# MCU.net
KiCad netlist of a schematic drawn in Altium Designer
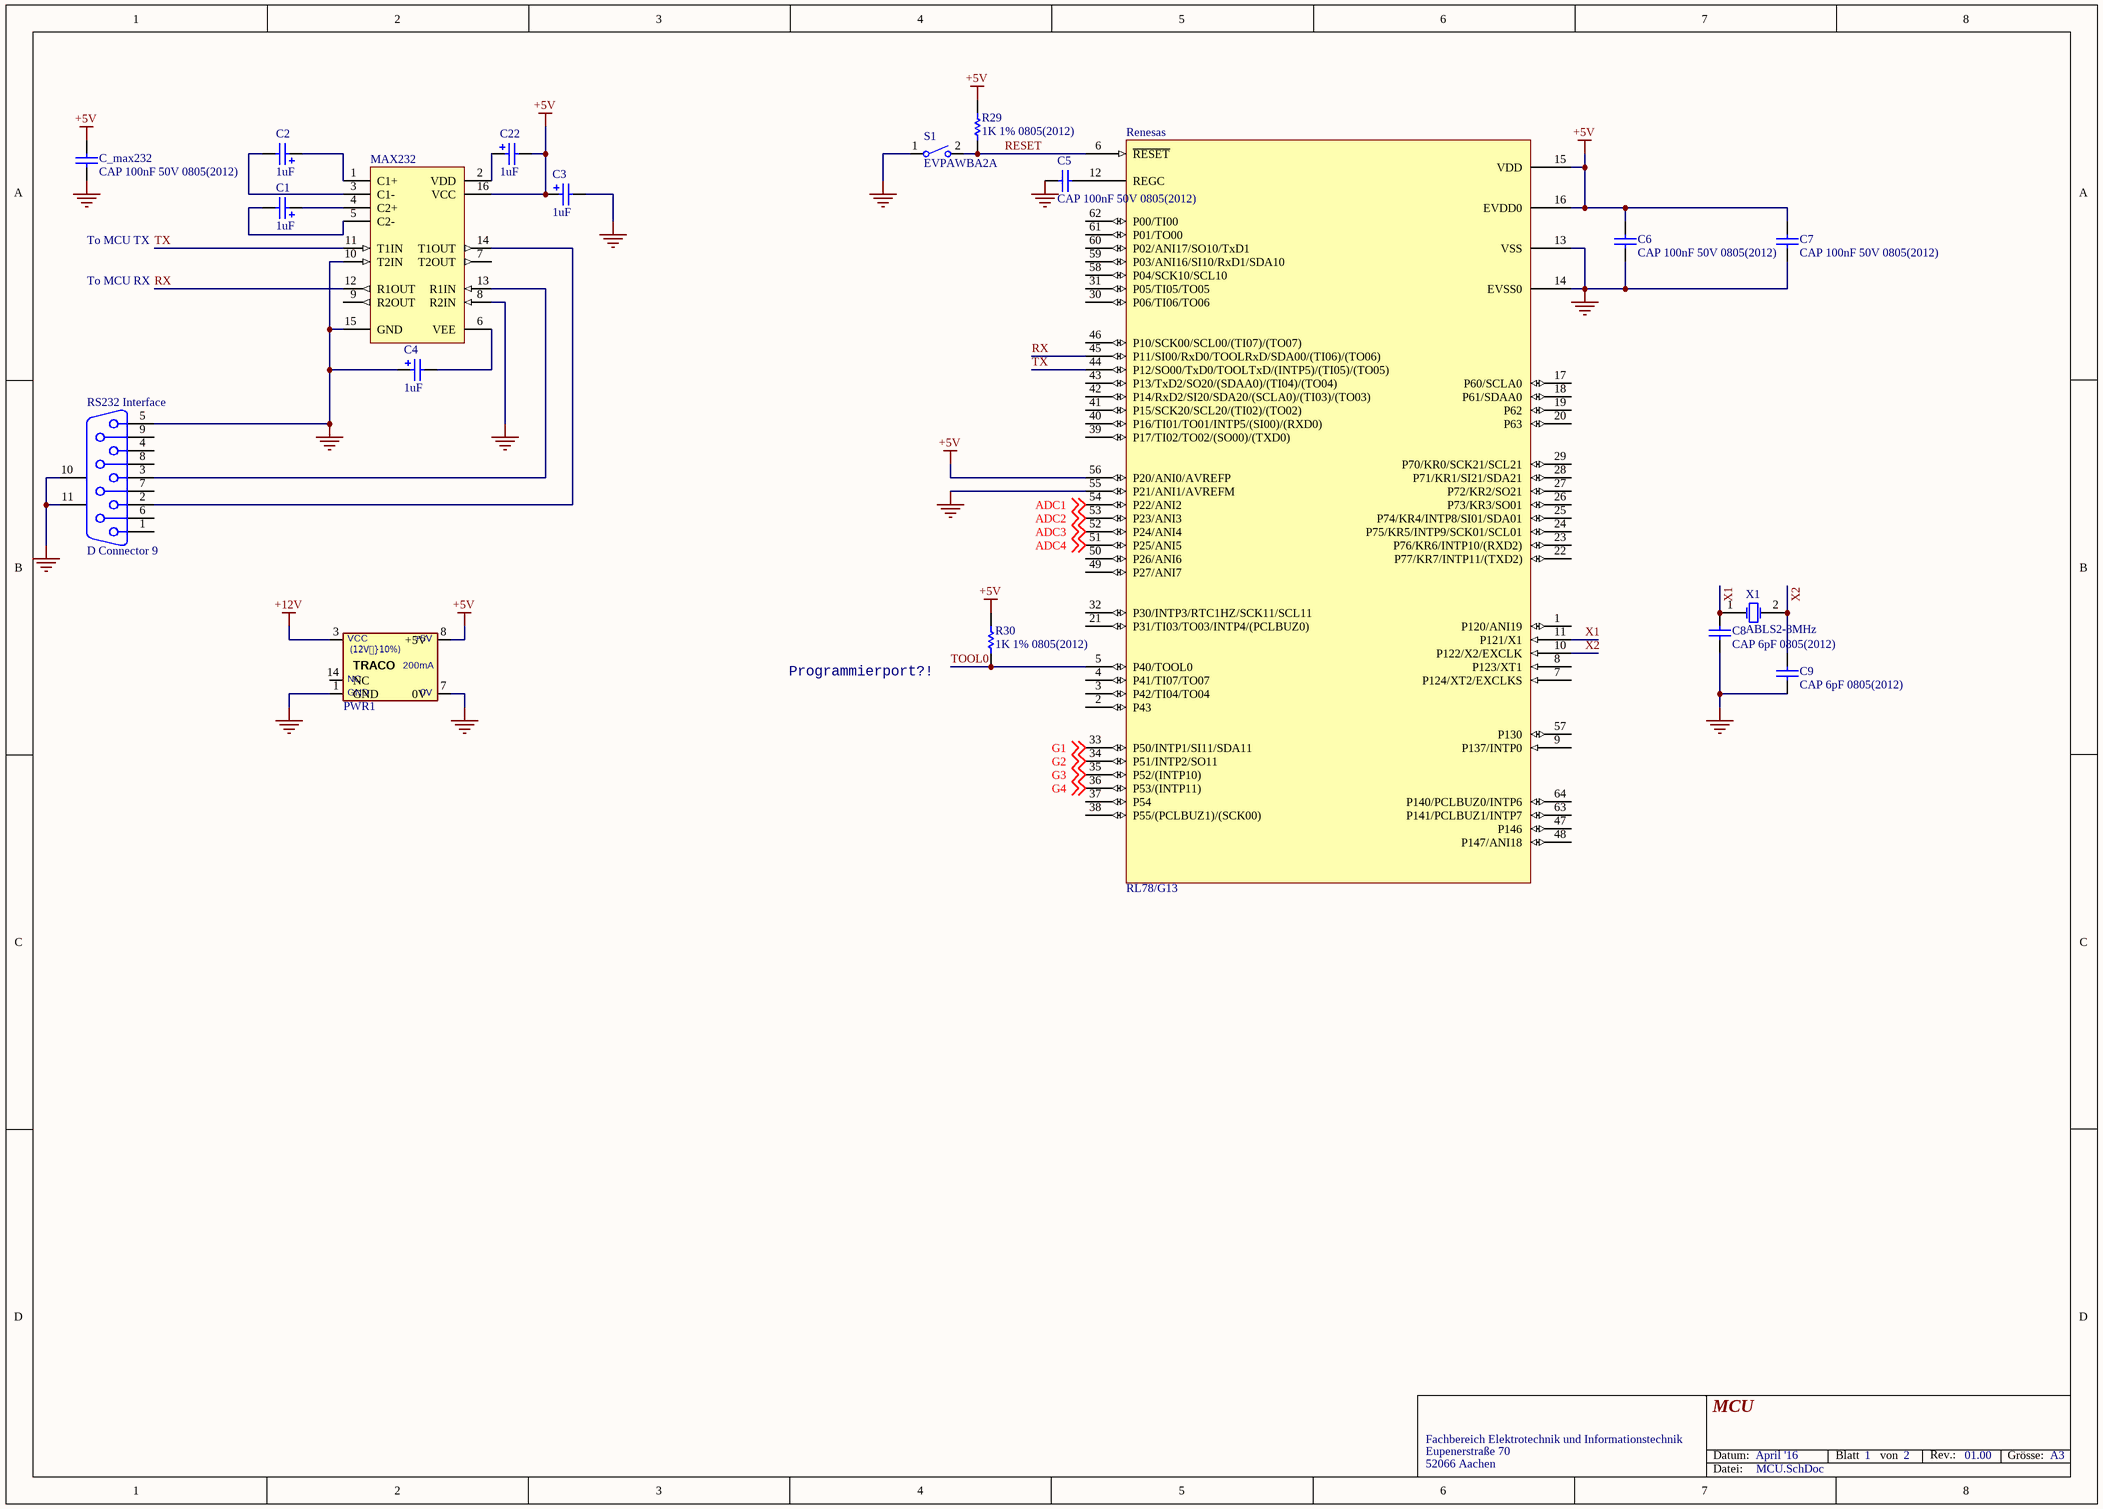
[diagram p0: MCU.SchDoc]

(export (version "E")
  (design (tool "Eeschema 10.0.6"))
  (components
    (comp (ref "C1")
      (value "1uF")
      (footprint "CC2012-0805")
      (description "Polarized Capacitor (Surface Mount)")
      (fields (field (name "Comment") "Cap Pol3") (field (name "PUBLISHER") "Altium Limited"))
      (libsource (lib "Miscellaneous Devices") (part "Cap Pol3"))
    )
    (comp (ref "C2")
      (value "1uF")
      (footprint "CC2012-0805")
      (description "Polarized Capacitor (Surface Mount)")
      (fields (field (name "Comment") "Cap Pol3") (field (name "PUBLISHER") "Altium Limited"))
      (libsource (lib "Miscellaneous Devices") (part "Cap Pol3"))
    )
    (comp (ref "C3")
      (value "1uF")
      (footprint "CC2012-0805")
      (description "Polarized Capacitor (Surface Mount)")
      (fields (field (name "Comment") "Cap Pol3") (field (name "PUBLISHER") "Altium Limited"))
      (libsource (lib "Miscellaneous Devices") (part "Cap Pol3"))
    )
    (comp (ref "C4")
      (value "1uF")
      (footprint "CC2012-0805")
      (description "Polarized Capacitor (Surface Mount)")
      (fields (field (name "Comment") "Cap Pol3") (field (name "PUBLISHER") "Altium Limited"))
      (libsource (lib "Miscellaneous Devices") (part "Cap Pol3"))
    )
    (comp (ref "C5")
      (value "CAP 100nF 50V 0805(2012)")
      (footprint "CAPC0805(2012)145_M")
      (description "CAP 100nF 50V ±10% 0805 (2012 Metric) Thickness 1.45mm SMD")
      (fields (field (name "TOLERANCE") "Â±10%"))
      (libsource (lib "Altium Content Vault") (part "CAP"))
    )
    (comp (ref "C6")
      (value "CAP 100nF 50V 0805(2012)")
      (footprint "CAPC0805(2012)145_M")
      (description "CAP 100nF 50V ±10% 0805 (2012 Metric) Thickness 1.45mm SMD")
      (fields (field (name "TOLERANCE") "Â±10%"))
      (libsource (lib "Altium Content Vault") (part "CAP"))
    )
    (comp (ref "C7")
      (value "CAP 100nF 50V 0805(2012)")
      (footprint "CAPC0805(2012)145_M")
      (description "CAP 100nF 50V ±10% 0805 (2012 Metric) Thickness 1.45mm SMD")
      (fields (field (name "TOLERANCE") "Â±10%"))
      (libsource (lib "Altium Content Vault") (part "CAP"))
    )
    (comp (ref "C8")
      (value "CAP 6pF 0805(2012)")
      (footprint "CAPC0805(2012)145_M")
      (description "CAP 100nF 50V ±10% 0805 (2012 Metric) Thickness 1.45mm SMD")
      (fields (field (name "TOLERANCE") "Â±10%"))
      (libsource (lib "Altium Content Vault") (part "CAP"))
    )
    (comp (ref "C9")
      (value "CAP 6pF 0805(2012)")
      (footprint "CAPC0805(2012)145_M")
      (description "CAP 100nF 50V ±10% 0805 (2012 Metric) Thickness 1.45mm SMD")
      (fields (field (name "TOLERANCE") "Â±10%"))
      (libsource (lib "Altium Content Vault") (part "CAP"))
    )
    (comp (ref "C22")
      (value "1uF")
      (footprint "CC2012-0805")
      (description "Polarized Capacitor (Surface Mount)")
      (fields (field (name "Comment") "Cap Pol3") (field (name "PUBLISHER") "Altium Limited"))
      (libsource (lib "Miscellaneous Devices") (part "Cap Pol3"))
    )
    (comp (ref "C_max232")
      (value "CAP 100nF 50V 0805(2012)")
      (footprint "CAPC0805(2012)145_M")
      (description "CAP 100nF 50V ±10% 0805 (2012 Metric) Thickness 1.45mm SMD")
      (fields (field (name "TOLERANCE") "Â±10%"))
      (libsource (lib "Altium Content Vault") (part "CAP"))
    )
    (comp (ref "MAX232")
      (value "MAX232CSE")
      (footprint "NSO16")
      (description "+5V Powered, Multi-Channel RS-232 Driver/Receiver")
      (fields (field (name "PUBLISHER") "Altium Limited"))
      (libsource (lib "Maxim Communication Transceiver") (part "MAX232CSE"))
    )
    (comp (ref "PWR1")
      (value "TES1-1211")
      (footprint "TES14")
      (description "Input=12V}10% Output=5V 200mA 1W 1500VDC Isolation SMD14 RoHS")
      (libsource (lib "TRACO_TES1_e") (part "TES1-1211"))
    )
    (comp (ref "R29")
      (value "1K 1% 0805(2012)")
      (footprint "RESC0805(2012)_M")
      (description "10K 0.125W 1% 0805 (2012 Metric)  SMD")
      (fields (field (name "TOLERANCE") "1 %") (field (name "POWER") "0.125 W"))
      (libsource (lib "Altium Content Vault") (part "CMP-1013-00623-1"))
    )
    (comp (ref "R30")
      (value "1K 1% 0805(2012)")
      (footprint "RESC0805(2012)_M")
      (description "10K 0.125W 1% 0805 (2012 Metric)  SMD")
      (fields (field (name "TOLERANCE") "1 %") (field (name "POWER") "0.125 W"))
      (libsource (lib "Altium Content Vault") (part "CMP-1013-00623-1"))
    )
    (comp (ref "Renesas")
      (value "RL78/G13")
      (footprint "R5F100LEAFA - duplicate")
      (libsource (lib "RenesasRL78") (part "RL78/G13"))
    )
    (comp (ref "RS232 Interface")
      (value "D Connector 9")
      (footprint "DSUB1.385-2H9")
      (description "Receptacle Assembly, 9 Position, Right Angle")
      (fields (field (name "PUBLISHER") "Altium Limited"))
      (libsource (lib "Miscellaneous Connectors") (part "D Connector 9"))
    )
    (comp (ref "S1")
      (value "EVPAWBA2A")
      (footprint "PNSC-EVPAW_V")
      (fields (field (name "MANUFACTURER") "Panasonic"))
      (libsource (lib "Altium Content Vault") (part "PNSC-SPST-2"))
    )
    (comp (ref "X1")
      (value "ABLS2-8MHz")
      (footprint "ABRA-ABLS2-2_V")
      (fields (field (name "MANUFACTURER") "Abracon") (field (name "PARTNUMBER") "ABLS2-4.096MHZ-D4Y-T"))
      (libsource (lib "Altium Content Vault") (part "ABRA-XTAL_1-2-2"))
    )
  )
  (nets
    (net (code "1") (name "+5V") (class "Default")
      (node (ref "C22") (pin "2") (pinfunction "2_2") (pintype "passive"))
      (node (ref "C3") (pin "1") (pinfunction "1_1") (pintype "passive"))
      (node (ref "C6") (pin "2") (pinfunction "2_2") (pintype "passive"))
      (node (ref "C7") (pin "2") (pinfunction "2_2") (pintype "passive"))
      (node (ref "C_max232") (pin "2") (pinfunction "2_2") (pintype "passive"))
      (node (ref "MAX232") (pin "16") (pinfunction "VCC_16") (pintype "power_in"))
      (node (ref "PWR1") (pin "8") (pinfunction "+5V_8") (pintype "power_in"))
      (node (ref "R29") (pin "1") (pinfunction "1_1") (pintype "passive"))
      (node (ref "R30") (pin "1") (pinfunction "1_1") (pintype "passive"))
      (node (ref "Renesas") (pin "15") (pinfunction "VDD_15") (pintype "power_in"))
      (node (ref "Renesas") (pin "16") (pinfunction "EVDD0_16") (pintype "power_in"))
      (node (ref "Renesas") (pin "56") (pinfunction "P20/ANI0/AVREFP_56") (pintype "bidirectional"))
    )
    (net (code "2") (name "+12V") (class "Default")
      (node (ref "PWR1") (pin "3") (pinfunction "VCC_3") (pintype "power_in"))
    )
    (net (code "3") (name "/RESET") (class "Default")
      (node (ref "R29") (pin "2") (pinfunction "2_2") (pintype "passive"))
      (node (ref "Renesas") (pin "6") (pinfunction "~{RESET}_6") (pintype "input"))
      (node (ref "S1") (pin "2") (pinfunction "B1_2") (pintype "passive"))
    )
    (net (code "4") (name "/RX") (class "Default")
      (node (ref "MAX232") (pin "12") (pinfunction "R1OUT_12") (pintype "output"))
      (node (ref "Renesas") (pin "45") (pinfunction "P11/SI00/RxD0/TOOLRxD/SDA00/(TI06)/(TO06)_45") (pintype "bidirectional"))
    )
    (net (code "5") (name "/TOOL0") (class "Default")
      (node (ref "R30") (pin "2") (pinfunction "2_2") (pintype "passive"))
      (node (ref "Renesas") (pin "5") (pinfunction "P40/TOOL0_5") (pintype "bidirectional"))
    )
    (net (code "6") (name "/TX") (class "Default")
      (node (ref "MAX232") (pin "11") (pinfunction "T1IN_11") (pintype "input"))
      (node (ref "Renesas") (pin "44") (pinfunction "P12/SO00/TxD0/TOOLTxD/(INTP5)/(TI05)/(TO05)_44") (pintype "bidirectional"))
    )
    (net (code "7") (name "/X1") (class "Default")
      (node (ref "C8") (pin "2") (pinfunction "2_2") (pintype "passive"))
      (node (ref "Renesas") (pin "11") (pinfunction "P121/X1_11") (pintype "input"))
      (node (ref "X1") (pin "1") (pinfunction "X1_1") (pintype "passive"))
    )
    (net (code "8") (name "/X2") (class "Default")
      (node (ref "C9") (pin "2") (pinfunction "2_2") (pintype "passive"))
      (node (ref "Renesas") (pin "10") (pinfunction "P122/X2/EXCLK_10") (pintype "input"))
      (node (ref "X1") (pin "2") (pinfunction "X2_2") (pintype "passive"))
    )
    (net (code "9") (name "ADC1") (class "Default")
      (node (ref "Renesas") (pin "54") (pinfunction "P22/ANI2_54") (pintype "bidirectional"))
    )
    (net (code "10") (name "ADC2") (class "Default")
      (node (ref "Renesas") (pin "53") (pinfunction "P23/ANI3_53") (pintype "bidirectional"))
    )
    (net (code "11") (name "ADC3") (class "Default")
      (node (ref "Renesas") (pin "52") (pinfunction "P24/ANI4_52") (pintype "bidirectional"))
    )
    (net (code "12") (name "ADC4") (class "Default")
      (node (ref "Renesas") (pin "51") (pinfunction "P25/ANI5_51") (pintype "bidirectional"))
    )
    (net (code "13") (name "G1") (class "Default")
      (node (ref "Renesas") (pin "33") (pinfunction "P50/INTP1/SI11/SDA11_33") (pintype "bidirectional"))
    )
    (net (code "14") (name "G2") (class "Default")
      (node (ref "Renesas") (pin "34") (pinfunction "P51/INTP2/SO11_34") (pintype "bidirectional"))
    )
    (net (code "15") (name "G3") (class "Default")
      (node (ref "Renesas") (pin "35") (pinfunction "P52/(INTP10)_35") (pintype "bidirectional"))
    )
    (net (code "16") (name "G4") (class "Default")
      (node (ref "Renesas") (pin "36") (pinfunction "P53/(INTP11)_36") (pintype "bidirectional"))
    )
    (net (code "17") (name "GND") (class "Default")
      (node (ref "C3") (pin "2") (pinfunction "2_2") (pintype "passive"))
      (node (ref "C4") (pin "1") (pinfunction "1_1") (pintype "passive"))
      (node (ref "C5") (pin "2") (pinfunction "2_2") (pintype "passive"))
      (node (ref "C6") (pin "1") (pinfunction "1_1") (pintype "passive"))
      (node (ref "C7") (pin "1") (pinfunction "1_1") (pintype "passive"))
      (node (ref "C8") (pin "1") (pinfunction "1_1") (pintype "passive"))
      (node (ref "C9") (pin "1") (pinfunction "1_1") (pintype "passive"))
      (node (ref "C_max232") (pin "1") (pinfunction "1_1") (pintype "passive"))
      (node (ref "MAX232") (pin "10") (pinfunction "T2IN_10") (pintype "input"))
      (node (ref "MAX232") (pin "15") (pinfunction "GND_15") (pintype "power_in"))
      (node (ref "MAX232") (pin "8") (pinfunction "R2IN_8") (pintype "input"))
      (node (ref "PWR1") (pin "1") (pinfunction "GND_1") (pintype "power_in"))
      (node (ref "PWR1") (pin "7") (pinfunction "0V_7") (pintype "power_in"))
      (node (ref "RS232 Interface") (pin "10") (pinfunction "MH1_10") (pintype "passive"))
      (node (ref "RS232 Interface") (pin "11") (pinfunction "MH2_11") (pintype "passive"))
      (node (ref "RS232 Interface") (pin "5") (pinfunction "5_5") (pintype "passive"))
      (node (ref "Renesas") (pin "13") (pinfunction "VSS_13") (pintype "power_in"))
      (node (ref "Renesas") (pin "14") (pinfunction "EVSS0_14") (pintype "power_in"))
      (node (ref "Renesas") (pin "55") (pinfunction "P21/ANI1/AVREFM_55") (pintype "bidirectional"))
      (node (ref "S1") (pin "1") (pinfunction "A1_1") (pintype "passive"))
    )
    (net (code "18") (name "Net-(MAX232-C1+)") (class "Default")
      (node (ref "C2") (pin "1") (pinfunction "1_1") (pintype "passive"))
      (node (ref "MAX232") (pin "1") (pinfunction "C1+_1") (pintype "passive"))
    )
    (net (code "19") (name "Net-(MAX232-C1-)") (class "Default")
      (node (ref "C2") (pin "2") (pinfunction "2_2") (pintype "passive"))
      (node (ref "MAX232") (pin "3") (pinfunction "C1-_3") (pintype "passive"))
    )
    (net (code "20") (name "Net-(MAX232-C2+)") (class "Default")
      (node (ref "C1") (pin "1") (pinfunction "1_1") (pintype "passive"))
      (node (ref "MAX232") (pin "4") (pinfunction "C2+_4") (pintype "passive"))
    )
    (net (code "21") (name "Net-(MAX232-C2-)") (class "Default")
      (node (ref "C1") (pin "2") (pinfunction "2_2") (pintype "passive"))
      (node (ref "MAX232") (pin "5") (pinfunction "C2-_5") (pintype "passive"))
    )
    (net (code "22") (name "Net-(MAX232-R1IN)") (class "Default")
      (node (ref "MAX232") (pin "13") (pinfunction "R1IN_13") (pintype "input"))
      (node (ref "RS232 Interface") (pin "3") (pinfunction "3_3") (pintype "passive"))
    )
    (net (code "23") (name "Net-(MAX232-T1OUT)") (class "Default")
      (node (ref "MAX232") (pin "14") (pinfunction "T1OUT_14") (pintype "output"))
      (node (ref "RS232 Interface") (pin "2") (pinfunction "2_2") (pintype "passive"))
    )
    (net (code "24") (name "Net-(MAX232-VDD)") (class "Default")
      (node (ref "C22") (pin "1") (pinfunction "1_1") (pintype "passive"))
      (node (ref "MAX232") (pin "2") (pinfunction "VDD_2") (pintype "power_in"))
    )
    (net (code "25") (name "Net-(MAX232-VEE)") (class "Default")
      (node (ref "C4") (pin "2") (pinfunction "2_2") (pintype "passive"))
      (node (ref "MAX232") (pin "6") (pinfunction "VEE_6") (pintype "power_in"))
    )
    (net (code "26") (name "Net-(Renesas-REGC)") (class "Default")
      (node (ref "C5") (pin "1") (pinfunction "1_1") (pintype "passive"))
      (node (ref "Renesas") (pin "12") (pinfunction "REGC_12") (pintype "passive"))
    )
    (net (code "27") (name "unconnected-(MAX232-R2OUT-Pad9)") (class "Default")
      (node (ref "MAX232") (pin "9") (pinfunction "R2OUT_9") (pintype "output"))
    )
    (net (code "28") (name "unconnected-(MAX232-T2OUT-Pad7)") (class "Default")
      (node (ref "MAX232") (pin "7") (pinfunction "T2OUT_7") (pintype "output"))
    )
    (net (code "29") (name "unconnected-(PWR1-NC-Pad14)") (class "Default")
      (node (ref "PWR1") (pin "14") (pinfunction "NC_14") (pintype "passive"))
    )
    (net (code "30") (name "unconnected-(RS232 Interface-Pad1)") (class "Default")
      (node (ref "RS232 Interface") (pin "1") (pinfunction "1_1") (pintype "passive"))
    )
    (net (code "31") (name "unconnected-(RS232 Interface-Pad4)") (class "Default")
      (node (ref "RS232 Interface") (pin "4") (pinfunction "4_4") (pintype "passive"))
    )
    (net (code "32") (name "unconnected-(RS232 Interface-Pad6)") (class "Default")
      (node (ref "RS232 Interface") (pin "6") (pinfunction "6_6") (pintype "passive"))
    )
    (net (code "33") (name "unconnected-(RS232 Interface-Pad7)") (class "Default")
      (node (ref "RS232 Interface") (pin "7") (pinfunction "7_7") (pintype "passive"))
    )
    (net (code "34") (name "unconnected-(RS232 Interface-Pad8)") (class "Default")
      (node (ref "RS232 Interface") (pin "8") (pinfunction "8_8") (pintype "passive"))
    )
    (net (code "35") (name "unconnected-(RS232 Interface-Pad9)") (class "Default")
      (node (ref "RS232 Interface") (pin "9") (pinfunction "9_9") (pintype "passive"))
    )
    (net (code "36") (name "unconnected-(Renesas-P00{slash}TI00-Pad62)") (class "Default")
      (node (ref "Renesas") (pin "62") (pinfunction "P00/TI00_62") (pintype "bidirectional"))
    )
    (net (code "37") (name "unconnected-(Renesas-P01{slash}TO00-Pad61)") (class "Default")
      (node (ref "Renesas") (pin "61") (pinfunction "P01/TO00_61") (pintype "bidirectional"))
    )
    (net (code "38") (name "unconnected-(Renesas-P02{slash}ANI17{slash}SO10{slash}TxD1-Pad60)") (class "Default")
      (node (ref "Renesas") (pin "60") (pinfunction "P02/ANI17/SO10/TxD1_60") (pintype "bidirectional"))
    )
    (net (code "39") (name "unconnected-(Renesas-P03{slash}ANI16{slash}SI10{slash}RxD1{slash}SDA10-Pad59)") (class "Default")
      (node (ref "Renesas") (pin "59") (pinfunction "P03/ANI16/SI10/RxD1/SDA10_59") (pintype "bidirectional"))
    )
    (net (code "40") (name "unconnected-(Renesas-P04{slash}SCK10{slash}SCL10-Pad58)") (class "Default")
      (node (ref "Renesas") (pin "58") (pinfunction "P04/SCK10/SCL10_58") (pintype "bidirectional"))
    )
    (net (code "41") (name "unconnected-(Renesas-P05{slash}TI05{slash}TO05-Pad31)") (class "Default")
      (node (ref "Renesas") (pin "31") (pinfunction "P05/TI05/TO05_31") (pintype "bidirectional"))
    )
    (net (code "42") (name "unconnected-(Renesas-P06{slash}TI06{slash}TO06-Pad30)") (class "Default")
      (node (ref "Renesas") (pin "30") (pinfunction "P06/TI06/TO06_30") (pintype "bidirectional"))
    )
    (net (code "43") (name "unconnected-(Renesas-P10{slash}SCK00{slash}SCL00{slash}(TI07){slash}(TO07)-Pad46)") (class "Default")
      (node (ref "Renesas") (pin "46") (pinfunction "P10/SCK00/SCL00/(TI07)/(TO07)_46") (pintype "bidirectional"))
    )
    (net (code "44") (name "unconnected-(Renesas-P13{slash}TxD2{slash}SO20{slash}(SDAA0){slash}(TI04){slash}(TO04)-Pad43)") (class "Default")
      (node (ref "Renesas") (pin "43") (pinfunction "P13/TxD2/SO20/(SDAA0)/(TI04)/(TO04)_43") (pintype "bidirectional"))
    )
    (net (code "45") (name "unconnected-(Renesas-P14{slash}RxD2{slash}SI20{slash}SDA20{slash}(SCLA0){slash}(TI03){slash}(TO03)-Pad42)") (class "Default")
      (node (ref "Renesas") (pin "42") (pinfunction "P14/RxD2/SI20/SDA20/(SCLA0)/(TI03)/(TO03)_42") (pintype "bidirectional"))
    )
    (net (code "46") (name "unconnected-(Renesas-P15{slash}SCK20{slash}SCL20{slash}(TI02){slash}(TO02)-Pad41)") (class "Default")
      (node (ref "Renesas") (pin "41") (pinfunction "P15/SCK20/SCL20/(TI02)/(TO02)_41") (pintype "bidirectional"))
    )
    (net (code "47") (name "unconnected-(Renesas-P16{slash}TI01{slash}TO01{slash}INTP5{slash}(SI00){slash}(RXD0)-Pad40)") (class "Default")
      (node (ref "Renesas") (pin "40") (pinfunction "P16/TI01/TO01/INTP5/(SI00)/(RXD0)_40") (pintype "bidirectional"))
    )
    (net (code "48") (name "unconnected-(Renesas-P17{slash}TI02{slash}TO02{slash}(SO00){slash}(TXD0)-Pad39)") (class "Default")
      (node (ref "Renesas") (pin "39") (pinfunction "P17/TI02/TO02/(SO00)/(TXD0)_39") (pintype "bidirectional"))
    )
    (net (code "49") (name "unconnected-(Renesas-P26{slash}ANI6-Pad50)") (class "Default")
      (node (ref "Renesas") (pin "50") (pinfunction "P26/ANI6_50") (pintype "bidirectional"))
    )
    (net (code "50") (name "unconnected-(Renesas-P27{slash}ANI7-Pad49)") (class "Default")
      (node (ref "Renesas") (pin "49") (pinfunction "P27/ANI7_49") (pintype "bidirectional"))
    )
    (net (code "51") (name "unconnected-(Renesas-P30{slash}INTP3{slash}RTC1HZ{slash}SCK11{slash}SCL11-Pad32)") (class "Default")
      (node (ref "Renesas") (pin "32") (pinfunction "P30/INTP3/RTC1HZ/SCK11/SCL11_32") (pintype "bidirectional"))
    )
    (net (code "52") (name "unconnected-(Renesas-P31{slash}TI03{slash}TO03{slash}INTP4{slash}(PCLBUZ0)-Pad21)") (class "Default")
      (node (ref "Renesas") (pin "21") (pinfunction "P31/TI03/TO03/INTP4/(PCLBUZ0)_21") (pintype "bidirectional"))
    )
    (net (code "53") (name "unconnected-(Renesas-P41{slash}TI07{slash}TO07-Pad4)") (class "Default")
      (node (ref "Renesas") (pin "4") (pinfunction "P41/TI07/TO07_4") (pintype "bidirectional"))
    )
    (net (code "54") (name "unconnected-(Renesas-P42{slash}TI04{slash}TO04-Pad3)") (class "Default")
      (node (ref "Renesas") (pin "3") (pinfunction "P42/TI04/TO04_3") (pintype "bidirectional"))
    )
    (net (code "55") (name "unconnected-(Renesas-P43-Pad2)") (class "Default")
      (node (ref "Renesas") (pin "2") (pinfunction "P43_2") (pintype "bidirectional"))
    )
    (net (code "56") (name "unconnected-(Renesas-P54-Pad37)") (class "Default")
      (node (ref "Renesas") (pin "37") (pinfunction "P54_37") (pintype "bidirectional"))
    )
    (net (code "57") (name "unconnected-(Renesas-P55{slash}(PCLBUZ1){slash}(SCK00)-Pad38)") (class "Default")
      (node (ref "Renesas") (pin "38") (pinfunction "P55/(PCLBUZ1)/(SCK00)_38") (pintype "bidirectional"))
    )
    (net (code "58") (name "unconnected-(Renesas-P60{slash}SCLA0-Pad17)") (class "Default")
      (node (ref "Renesas") (pin "17") (pinfunction "P60/SCLA0_17") (pintype "bidirectional"))
    )
    (net (code "59") (name "unconnected-(Renesas-P61{slash}SDAA0-Pad18)") (class "Default")
      (node (ref "Renesas") (pin "18") (pinfunction "P61/SDAA0_18") (pintype "bidirectional"))
    )
    (net (code "60") (name "unconnected-(Renesas-P62-Pad19)") (class "Default")
      (node (ref "Renesas") (pin "19") (pinfunction "P62_19") (pintype "bidirectional"))
    )
    (net (code "61") (name "unconnected-(Renesas-P63-Pad20)") (class "Default")
      (node (ref "Renesas") (pin "20") (pinfunction "P63_20") (pintype "bidirectional"))
    )
    (net (code "62") (name "unconnected-(Renesas-P70{slash}KR0{slash}SCK21{slash}SCL21-Pad29)") (class "Default")
      (node (ref "Renesas") (pin "29") (pinfunction "P70/KR0/SCK21/SCL21_29") (pintype "bidirectional"))
    )
    (net (code "63") (name "unconnected-(Renesas-P71{slash}KR1{slash}SI21{slash}SDA21-Pad28)") (class "Default")
      (node (ref "Renesas") (pin "28") (pinfunction "P71/KR1/SI21/SDA21_28") (pintype "bidirectional"))
    )
    (net (code "64") (name "unconnected-(Renesas-P72{slash}KR2{slash}SO21-Pad27)") (class "Default")
      (node (ref "Renesas") (pin "27") (pinfunction "P72/KR2/SO21_27") (pintype "bidirectional"))
    )
    (net (code "65") (name "unconnected-(Renesas-P73{slash}KR3{slash}SO01-Pad26)") (class "Default")
      (node (ref "Renesas") (pin "26") (pinfunction "P73/KR3/SO01_26") (pintype "bidirectional"))
    )
    (net (code "66") (name "unconnected-(Renesas-P74{slash}KR4{slash}INTP8{slash}SI01{slash}SDA01-Pad25)") (class "Default")
      (node (ref "Renesas") (pin "25") (pinfunction "P74/KR4/INTP8/SI01/SDA01_25") (pintype "bidirectional"))
    )
    (net (code "67") (name "unconnected-(Renesas-P75{slash}KR5{slash}INTP9{slash}SCK01{slash}SCL01-Pad24)") (class "Default")
      (node (ref "Renesas") (pin "24") (pinfunction "P75/KR5/INTP9/SCK01/SCL01_24") (pintype "bidirectional"))
    )
    (net (code "68") (name "unconnected-(Renesas-P76{slash}KR6{slash}INTP10{slash}(RXD2)-Pad23)") (class "Default")
      (node (ref "Renesas") (pin "23") (pinfunction "P76/KR6/INTP10/(RXD2)_23") (pintype "bidirectional"))
    )
    (net (code "69") (name "unconnected-(Renesas-P77{slash}KR7{slash}INTP11{slash}(TXD2)-Pad22)") (class "Default")
      (node (ref "Renesas") (pin "22") (pinfunction "P77/KR7/INTP11/(TXD2)_22") (pintype "bidirectional"))
    )
    (net (code "70") (name "unconnected-(Renesas-P120{slash}ANI19-Pad1)") (class "Default")
      (node (ref "Renesas") (pin "1") (pinfunction "P120/ANI19_1") (pintype "bidirectional"))
    )
    (net (code "71") (name "unconnected-(Renesas-P123{slash}XT1-Pad8)") (class "Default")
      (node (ref "Renesas") (pin "8") (pinfunction "P123/XT1_8") (pintype "input"))
    )
    (net (code "72") (name "unconnected-(Renesas-P124{slash}XT2{slash}EXCLKS-Pad7)") (class "Default")
      (node (ref "Renesas") (pin "7") (pinfunction "P124/XT2/EXCLKS_7") (pintype "input"))
    )
    (net (code "73") (name "unconnected-(Renesas-P130-Pad57)") (class "Default")
      (node (ref "Renesas") (pin "57") (pinfunction "P130_57") (pintype "bidirectional"))
    )
    (net (code "74") (name "unconnected-(Renesas-P137{slash}INTP0-Pad9)") (class "Default")
      (node (ref "Renesas") (pin "9") (pinfunction "P137/INTP0_9") (pintype "input"))
    )
    (net (code "75") (name "unconnected-(Renesas-P140{slash}PCLBUZ0{slash}INTP6-Pad64)") (class "Default")
      (node (ref "Renesas") (pin "64") (pinfunction "P140/PCLBUZ0/INTP6_64") (pintype "bidirectional"))
    )
    (net (code "76") (name "unconnected-(Renesas-P141{slash}PCLBUZ1{slash}INTP7-Pad63)") (class "Default")
      (node (ref "Renesas") (pin "63") (pinfunction "P141/PCLBUZ1/INTP7_63") (pintype "bidirectional"))
    )
    (net (code "77") (name "unconnected-(Renesas-P146-Pad47)") (class "Default")
      (node (ref "Renesas") (pin "47") (pinfunction "P146_47") (pintype "bidirectional"))
    )
    (net (code "78") (name "unconnected-(Renesas-P147{slash}ANI18-Pad48)") (class "Default")
      (node (ref "Renesas") (pin "48") (pinfunction "P147/ANI18_48") (pintype "bidirectional"))
    )
  )
)
